# Familamp.net
KiCad netlist of a schematic drawn in EAGLE
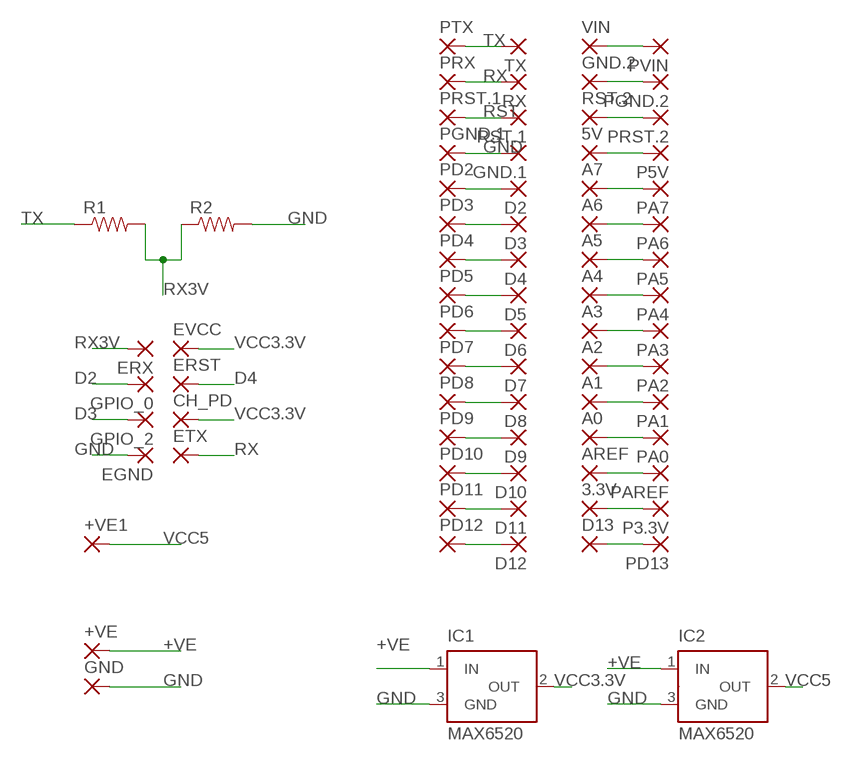
[diagram p0: schematic, sheet 1]

(export (version "E")
  (design (tool "Eeschema 10.0.6"))
  (components
    (comp (ref "+VE")
      (value "2,15/1,0")
      (footprint "eagle-import:2,15_1,0")
      (libsource (lib "eagle-import") (part "2,15/1,0"))
    )
    (comp (ref "+VE1")
      (value "2,15/1,0")
      (footprint "eagle-import:2,15_1,0")
      (libsource (lib "eagle-import") (part "2,15/1,0"))
    )
    (comp (ref "3.3V")
      (value "1,6/0,9")
      (footprint "eagle-import:1,6_0,9")
      (libsource (lib "eagle-import") (part "1,6/0,9"))
    )
    (comp (ref "5V")
      (value "1,6/0,9")
      (footprint "eagle-import:1,6_0,9")
      (libsource (lib "eagle-import") (part "1,6/0,9"))
    )
    (comp (ref "A0")
      (value "1,6/0,9")
      (footprint "eagle-import:1,6_0,9")
      (libsource (lib "eagle-import") (part "1,6/0,9"))
    )
    (comp (ref "A1")
      (value "1,6/0,9")
      (footprint "eagle-import:1,6_0,9")
      (libsource (lib "eagle-import") (part "1,6/0,9"))
    )
    (comp (ref "A2")
      (value "1,6/0,9")
      (footprint "eagle-import:1,6_0,9")
      (libsource (lib "eagle-import") (part "1,6/0,9"))
    )
    (comp (ref "A3")
      (value "1,6/0,9")
      (footprint "eagle-import:1,6_0,9")
      (libsource (lib "eagle-import") (part "1,6/0,9"))
    )
    (comp (ref "A4")
      (value "1,6/0,9")
      (footprint "eagle-import:1,6_0,9")
      (libsource (lib "eagle-import") (part "1,6/0,9"))
    )
    (comp (ref "A5")
      (value "1,6/0,9")
      (footprint "eagle-import:1,6_0,9")
      (libsource (lib "eagle-import") (part "1,6/0,9"))
    )
    (comp (ref "A6")
      (value "1,6/0,9")
      (footprint "eagle-import:1,6_0,9")
      (libsource (lib "eagle-import") (part "1,6/0,9"))
    )
    (comp (ref "A7")
      (value "1,6/0,9")
      (footprint "eagle-import:1,6_0,9")
      (libsource (lib "eagle-import") (part "1,6/0,9"))
    )
    (comp (ref "AREF")
      (value "1,6/0,9")
      (footprint "eagle-import:1,6_0,9")
      (libsource (lib "eagle-import") (part "1,6/0,9"))
    )
    (comp (ref "CH_PD")
      (value "2,15/1,0")
      (footprint "eagle-import:2,15_1,0")
      (libsource (lib "eagle-import") (part "2,15/1,0"))
    )
    (comp (ref "D2")
      (value "1,6/0,9")
      (footprint "eagle-import:1,6_0,9")
      (libsource (lib "eagle-import") (part "1,6/0,9"))
    )
    (comp (ref "D3")
      (value "1,6/0,9")
      (footprint "eagle-import:1,6_0,9")
      (libsource (lib "eagle-import") (part "1,6/0,9"))
    )
    (comp (ref "D4")
      (value "1,6/0,9")
      (footprint "eagle-import:1,6_0,9")
      (libsource (lib "eagle-import") (part "1,6/0,9"))
    )
    (comp (ref "D5")
      (value "1,6/0,9")
      (footprint "eagle-import:1,6_0,9")
      (libsource (lib "eagle-import") (part "1,6/0,9"))
    )
    (comp (ref "D6")
      (value "1,6/0,9")
      (footprint "eagle-import:1,6_0,9")
      (libsource (lib "eagle-import") (part "1,6/0,9"))
    )
    (comp (ref "D7")
      (value "1,6/0,9")
      (footprint "eagle-import:1,6_0,9")
      (libsource (lib "eagle-import") (part "1,6/0,9"))
    )
    (comp (ref "D8")
      (value "1,6/0,9")
      (footprint "eagle-import:1,6_0,9")
      (libsource (lib "eagle-import") (part "1,6/0,9"))
    )
    (comp (ref "D9")
      (value "1,6/0,9")
      (footprint "eagle-import:1,6_0,9")
      (libsource (lib "eagle-import") (part "1,6/0,9"))
    )
    (comp (ref "D10")
      (value "1,6/0,9")
      (footprint "eagle-import:1,6_0,9")
      (libsource (lib "eagle-import") (part "1,6/0,9"))
    )
    (comp (ref "D11")
      (value "1,6/0,9")
      (footprint "eagle-import:1,6_0,9")
      (libsource (lib "eagle-import") (part "1,6/0,9"))
    )
    (comp (ref "D12")
      (value "1,6/0,9")
      (footprint "eagle-import:1,6_0,9")
      (libsource (lib "eagle-import") (part "1,6/0,9"))
    )
    (comp (ref "D13")
      (value "1,6/0,9")
      (footprint "eagle-import:1,6_0,9")
      (libsource (lib "eagle-import") (part "1,6/0,9"))
    )
    (comp (ref "EGND")
      (value "2,15/1,0")
      (footprint "eagle-import:2,15_1,0")
      (libsource (lib "eagle-import") (part "2,15/1,0"))
    )
    (comp (ref "ERST")
      (value "2,15/1,0")
      (footprint "eagle-import:2,15_1,0")
      (libsource (lib "eagle-import") (part "2,15/1,0"))
    )
    (comp (ref "ERX")
      (value "2,15/1,0")
      (footprint "eagle-import:2,15_1,0")
      (libsource (lib "eagle-import") (part "2,15/1,0"))
    )
    (comp (ref "ETX")
      (value "2,15/1,0")
      (footprint "eagle-import:2,15_1,0")
      (libsource (lib "eagle-import") (part "2,15/1,0"))
    )
    (comp (ref "EVCC")
      (value "2,15/1,0")
      (footprint "eagle-import:2,15_1,0")
      (libsource (lib "eagle-import") (part "2,15/1,0"))
    )
    (comp (ref "GND")
      (value "2,15/1,0")
      (footprint "eagle-import:2,15_1,0")
      (libsource (lib "eagle-import") (part "2,15/1,0"))
    )
    (comp (ref "GND.1")
      (value "1,6/0,9")
      (footprint "eagle-import:1,6_0,9")
      (libsource (lib "eagle-import") (part "1,6/0,9"))
    )
    (comp (ref "GND.2")
      (value "1,6/0,9")
      (footprint "eagle-import:1,6_0,9")
      (libsource (lib "eagle-import") (part "1,6/0,9"))
    )
    (comp (ref "GPIO_0")
      (value "2,15/1,0")
      (footprint "eagle-import:2,15_1,0")
      (libsource (lib "eagle-import") (part "2,15/1,0"))
    )
    (comp (ref "GPIO_2")
      (value "2,15/1,0")
      (footprint "eagle-import:2,15_1,0")
      (libsource (lib "eagle-import") (part "2,15/1,0"))
    )
    (comp (ref "IC1")
      (value "MAX6520")
      (footprint "eagle-import:SOT23")
      (fields (field (name "MF") "MAXIM") (field (name "MPN") "MAX6520EUR-T"))
      (libsource (lib "eagle-import") (part "MAX6520"))
    )
    (comp (ref "IC2")
      (value "MAX6520")
      (footprint "eagle-import:SOT23")
      (fields (field (name "MF") "MAXIM") (field (name "MPN") "MAX6520EUR-T"))
      (libsource (lib "eagle-import") (part "MAX6520"))
    )
    (comp (ref "P3.3V")
      (value "1,6/0,9")
      (footprint "eagle-import:1,6_0,9")
      (libsource (lib "eagle-import") (part "1,6/0,9"))
    )
    (comp (ref "P5V")
      (value "1,6/0,9")
      (footprint "eagle-import:1,6_0,9")
      (libsource (lib "eagle-import") (part "1,6/0,9"))
    )
    (comp (ref "PA0")
      (value "1,6/0,9")
      (footprint "eagle-import:1,6_0,9")
      (libsource (lib "eagle-import") (part "1,6/0,9"))
    )
    (comp (ref "PA1")
      (value "1,6/0,9")
      (footprint "eagle-import:1,6_0,9")
      (libsource (lib "eagle-import") (part "1,6/0,9"))
    )
    (comp (ref "PA2")
      (value "1,6/0,9")
      (footprint "eagle-import:1,6_0,9")
      (libsource (lib "eagle-import") (part "1,6/0,9"))
    )
    (comp (ref "PA3")
      (value "1,6/0,9")
      (footprint "eagle-import:1,6_0,9")
      (libsource (lib "eagle-import") (part "1,6/0,9"))
    )
    (comp (ref "PA4")
      (value "1,6/0,9")
      (footprint "eagle-import:1,6_0,9")
      (libsource (lib "eagle-import") (part "1,6/0,9"))
    )
    (comp (ref "PA5")
      (value "1,6/0,9")
      (footprint "eagle-import:1,6_0,9")
      (libsource (lib "eagle-import") (part "1,6/0,9"))
    )
    (comp (ref "PA6")
      (value "1,6/0,9")
      (footprint "eagle-import:1,6_0,9")
      (libsource (lib "eagle-import") (part "1,6/0,9"))
    )
    (comp (ref "PA7")
      (value "1,6/0,9")
      (footprint "eagle-import:1,6_0,9")
      (libsource (lib "eagle-import") (part "1,6/0,9"))
    )
    (comp (ref "PAREF")
      (value "1,6/0,9")
      (footprint "eagle-import:1,6_0,9")
      (libsource (lib "eagle-import") (part "1,6/0,9"))
    )
    (comp (ref "PD2")
      (value "1,6/0,9")
      (footprint "eagle-import:1,6_0,9")
      (libsource (lib "eagle-import") (part "1,6/0,9"))
    )
    (comp (ref "PD3")
      (value "1,6/0,9")
      (footprint "eagle-import:1,6_0,9")
      (libsource (lib "eagle-import") (part "1,6/0,9"))
    )
    (comp (ref "PD4")
      (value "1,6/0,9")
      (footprint "eagle-import:1,6_0,9")
      (libsource (lib "eagle-import") (part "1,6/0,9"))
    )
    (comp (ref "PD5")
      (value "1,6/0,9")
      (footprint "eagle-import:1,6_0,9")
      (libsource (lib "eagle-import") (part "1,6/0,9"))
    )
    (comp (ref "PD6")
      (value "1,6/0,9")
      (footprint "eagle-import:1,6_0,9")
      (libsource (lib "eagle-import") (part "1,6/0,9"))
    )
    (comp (ref "PD7")
      (value "1,6/0,9")
      (footprint "eagle-import:1,6_0,9")
      (libsource (lib "eagle-import") (part "1,6/0,9"))
    )
    (comp (ref "PD8")
      (value "1,6/0,9")
      (footprint "eagle-import:1,6_0,9")
      (libsource (lib "eagle-import") (part "1,6/0,9"))
    )
    (comp (ref "PD9")
      (value "1,6/0,9")
      (footprint "eagle-import:1,6_0,9")
      (libsource (lib "eagle-import") (part "1,6/0,9"))
    )
    (comp (ref "PD10")
      (value "1,6/0,9")
      (footprint "eagle-import:1,6_0,9")
      (libsource (lib "eagle-import") (part "1,6/0,9"))
    )
    (comp (ref "PD11")
      (value "1,6/0,9")
      (footprint "eagle-import:1,6_0,9")
      (libsource (lib "eagle-import") (part "1,6/0,9"))
    )
    (comp (ref "PD12")
      (value "1,6/0,9")
      (footprint "eagle-import:1,6_0,9")
      (libsource (lib "eagle-import") (part "1,6/0,9"))
    )
    (comp (ref "PD13")
      (value "1,6/0,9")
      (footprint "eagle-import:1,6_0,9")
      (libsource (lib "eagle-import") (part "1,6/0,9"))
    )
    (comp (ref "PGND.1")
      (value "1,6/0,9")
      (footprint "eagle-import:1,6_0,9")
      (libsource (lib "eagle-import") (part "1,6/0,9"))
    )
    (comp (ref "PGND.2")
      (value "1,6/0,9")
      (footprint "eagle-import:1,6_0,9")
      (libsource (lib "eagle-import") (part "1,6/0,9"))
    )
    (comp (ref "PRST.1")
      (value "1,6/0,9")
      (footprint "eagle-import:1,6_0,9")
      (libsource (lib "eagle-import") (part "1,6/0,9"))
    )
    (comp (ref "PRST.2")
      (value "1,6/0,9")
      (footprint "eagle-import:1,6_0,9")
      (libsource (lib "eagle-import") (part "1,6/0,9"))
    )
    (comp (ref "PRX")
      (value "1,6/0,9")
      (footprint "eagle-import:1,6_0,9")
      (libsource (lib "eagle-import") (part "1,6/0,9"))
    )
    (comp (ref "PTX")
      (value "1,6/0,9")
      (footprint "eagle-import:1,6_0,9")
      (libsource (lib "eagle-import") (part "1,6/0,9"))
    )
    (comp (ref "PVIN")
      (value "1,6/0,9")
      (footprint "eagle-import:1,6_0,9")
      (libsource (lib "eagle-import") (part "1,6/0,9"))
    )
    (comp (ref "R1")
      (value "RESISTORPTH-1/2W")
      (footprint "eagle-import:AXIAL-0.5")
      (libsource (lib "eagle-import") (part "RESISTORPTH-1/2W"))
    )
    (comp (ref "R2")
      (value "RESISTORPTH-1/2W")
      (footprint "eagle-import:AXIAL-0.5")
      (libsource (lib "eagle-import") (part "RESISTORPTH-1/2W"))
    )
    (comp (ref "RST.1")
      (value "1,6/0,9")
      (footprint "eagle-import:1,6_0,9")
      (libsource (lib "eagle-import") (part "1,6/0,9"))
    )
    (comp (ref "RST.2")
      (value "1,6/0,9")
      (footprint "eagle-import:1,6_0,9")
      (libsource (lib "eagle-import") (part "1,6/0,9"))
    )
    (comp (ref "RX")
      (value "1,6/0,9")
      (footprint "eagle-import:1,6_0,9")
      (libsource (lib "eagle-import") (part "1,6/0,9"))
    )
    (comp (ref "TX")
      (value "1,6/0,9")
      (footprint "eagle-import:1,6_0,9")
      (libsource (lib "eagle-import") (part "1,6/0,9"))
    )
    (comp (ref "VIN")
      (value "1,6/0,9")
      (footprint "eagle-import:1,6_0,9")
      (libsource (lib "eagle-import") (part "1,6/0,9"))
    )
  )
  (nets
    (net (code "1") (name "/+VE") (class "Default")
      (node (ref "+VE") (pin "1") (pinfunction "P_1") (pintype "passive"))
      (node (ref "IC1") (pin "1") (pinfunction "IN_1") (pintype "input"))
      (node (ref "IC2") (pin "1") (pinfunction "IN_1") (pintype "input"))
      (node (ref "PVIN") (pin "1") (pinfunction "P_1") (pintype "passive"))
      (node (ref "VIN") (pin "1") (pinfunction "P_1") (pintype "passive"))
    )
    (net (code "2") (name "/D2") (class "Default")
      (node (ref "D2") (pin "1") (pinfunction "P_1") (pintype "passive"))
      (node (ref "GPIO_0") (pin "1") (pinfunction "P_1") (pintype "passive"))
      (node (ref "PD2") (pin "1") (pinfunction "P_1") (pintype "passive"))
    )
    (net (code "3") (name "/D3") (class "Default")
      (node (ref "D3") (pin "1") (pinfunction "P_1") (pintype "passive"))
      (node (ref "GPIO_2") (pin "1") (pinfunction "P_1") (pintype "passive"))
      (node (ref "PD3") (pin "1") (pinfunction "P_1") (pintype "passive"))
    )
    (net (code "4") (name "/D4") (class "Default")
      (node (ref "D4") (pin "1") (pinfunction "P_1") (pintype "passive"))
      (node (ref "ERST") (pin "1") (pinfunction "P_1") (pintype "passive"))
      (node (ref "PD4") (pin "1") (pinfunction "P_1") (pintype "passive"))
    )
    (net (code "5") (name "/GND") (class "Default")
      (node (ref "EGND") (pin "1") (pinfunction "P_1") (pintype "passive"))
      (node (ref "GND") (pin "1") (pinfunction "P_1") (pintype "passive"))
      (node (ref "GND.1") (pin "1") (pinfunction "P_1") (pintype "passive"))
      (node (ref "GND.2") (pin "1") (pinfunction "P_1") (pintype "passive"))
      (node (ref "IC1") (pin "3") (pinfunction "GND_3") (pintype "power_in"))
      (node (ref "IC2") (pin "3") (pinfunction "GND_3") (pintype "power_in"))
      (node (ref "PGND.1") (pin "1") (pinfunction "P_1") (pintype "passive"))
      (node (ref "PGND.2") (pin "1") (pinfunction "P_1") (pintype "passive"))
      (node (ref "R2") (pin "P$2") (pinfunction "2_P$2") (pintype "passive"))
    )
    (net (code "6") (name "/RST") (class "Default")
      (node (ref "PRST.1") (pin "1") (pinfunction "P_1") (pintype "passive"))
      (node (ref "RST.1") (pin "1") (pinfunction "P_1") (pintype "passive"))
    )
    (net (code "7") (name "/RX") (class "Default")
      (node (ref "ETX") (pin "1") (pinfunction "P_1") (pintype "passive"))
      (node (ref "PRX") (pin "1") (pinfunction "P_1") (pintype "passive"))
      (node (ref "RX") (pin "1") (pinfunction "P_1") (pintype "passive"))
    )
    (net (code "8") (name "/RX3V") (class "Default")
      (node (ref "ERX") (pin "1") (pinfunction "P_1") (pintype "passive"))
      (node (ref "R1") (pin "P$2") (pinfunction "2_P$2") (pintype "passive"))
      (node (ref "R2") (pin "P$1") (pinfunction "1_P$1") (pintype "passive"))
    )
    (net (code "9") (name "/TX") (class "Default")
      (node (ref "PTX") (pin "1") (pinfunction "P_1") (pintype "passive"))
      (node (ref "R1") (pin "P$1") (pinfunction "1_P$1") (pintype "passive"))
      (node (ref "TX") (pin "1") (pinfunction "P_1") (pintype "passive"))
    )
    (net (code "10") (name "/VCC3.3V") (class "Default")
      (node (ref "CH_PD") (pin "1") (pinfunction "P_1") (pintype "passive"))
      (node (ref "EVCC") (pin "1") (pinfunction "P_1") (pintype "passive"))
      (node (ref "IC1") (pin "2") (pinfunction "OUT_2") (pintype "output"))
    )
    (net (code "11") (name "/VCC5") (class "Default")
      (node (ref "+VE1") (pin "1") (pinfunction "P_1") (pintype "passive"))
      (node (ref "IC2") (pin "2") (pinfunction "OUT_2") (pintype "output"))
    )
    (net (code "12") (name "Net-(3.3V-P)") (class "Default")
      (node (ref "3.3V") (pin "1") (pinfunction "P_1") (pintype "passive"))
      (node (ref "P3.3V") (pin "1") (pinfunction "P_1") (pintype "passive"))
    )
    (net (code "13") (name "Net-(5V-P)") (class "Default")
      (node (ref "5V") (pin "1") (pinfunction "P_1") (pintype "passive"))
      (node (ref "P5V") (pin "1") (pinfunction "P_1") (pintype "passive"))
    )
    (net (code "14") (name "Net-(A0-P)") (class "Default")
      (node (ref "A0") (pin "1") (pinfunction "P_1") (pintype "passive"))
      (node (ref "PA0") (pin "1") (pinfunction "P_1") (pintype "passive"))
    )
    (net (code "15") (name "Net-(A1-P)") (class "Default")
      (node (ref "A1") (pin "1") (pinfunction "P_1") (pintype "passive"))
      (node (ref "PA1") (pin "1") (pinfunction "P_1") (pintype "passive"))
    )
    (net (code "16") (name "Net-(A2-P)") (class "Default")
      (node (ref "A2") (pin "1") (pinfunction "P_1") (pintype "passive"))
      (node (ref "PA2") (pin "1") (pinfunction "P_1") (pintype "passive"))
    )
    (net (code "17") (name "Net-(A3-P)") (class "Default")
      (node (ref "A3") (pin "1") (pinfunction "P_1") (pintype "passive"))
      (node (ref "PA3") (pin "1") (pinfunction "P_1") (pintype "passive"))
    )
    (net (code "18") (name "Net-(A4-P)") (class "Default")
      (node (ref "A4") (pin "1") (pinfunction "P_1") (pintype "passive"))
      (node (ref "PA4") (pin "1") (pinfunction "P_1") (pintype "passive"))
    )
    (net (code "19") (name "Net-(A5-P)") (class "Default")
      (node (ref "A5") (pin "1") (pinfunction "P_1") (pintype "passive"))
      (node (ref "PA5") (pin "1") (pinfunction "P_1") (pintype "passive"))
    )
    (net (code "20") (name "Net-(A6-P)") (class "Default")
      (node (ref "A6") (pin "1") (pinfunction "P_1") (pintype "passive"))
      (node (ref "PA6") (pin "1") (pinfunction "P_1") (pintype "passive"))
    )
    (net (code "21") (name "Net-(A7-P)") (class "Default")
      (node (ref "A7") (pin "1") (pinfunction "P_1") (pintype "passive"))
      (node (ref "PA7") (pin "1") (pinfunction "P_1") (pintype "passive"))
    )
    (net (code "22") (name "Net-(AREF-P)") (class "Default")
      (node (ref "AREF") (pin "1") (pinfunction "P_1") (pintype "passive"))
      (node (ref "PAREF") (pin "1") (pinfunction "P_1") (pintype "passive"))
    )
    (net (code "23") (name "Net-(D5-P)") (class "Default")
      (node (ref "D5") (pin "1") (pinfunction "P_1") (pintype "passive"))
      (node (ref "PD5") (pin "1") (pinfunction "P_1") (pintype "passive"))
    )
    (net (code "24") (name "Net-(D6-P)") (class "Default")
      (node (ref "D6") (pin "1") (pinfunction "P_1") (pintype "passive"))
      (node (ref "PD6") (pin "1") (pinfunction "P_1") (pintype "passive"))
    )
    (net (code "25") (name "Net-(D7-P)") (class "Default")
      (node (ref "D7") (pin "1") (pinfunction "P_1") (pintype "passive"))
      (node (ref "PD7") (pin "1") (pinfunction "P_1") (pintype "passive"))
    )
    (net (code "26") (name "Net-(D8-P)") (class "Default")
      (node (ref "D8") (pin "1") (pinfunction "P_1") (pintype "passive"))
      (node (ref "PD8") (pin "1") (pinfunction "P_1") (pintype "passive"))
    )
    (net (code "27") (name "Net-(D9-P)") (class "Default")
      (node (ref "D9") (pin "1") (pinfunction "P_1") (pintype "passive"))
      (node (ref "PD9") (pin "1") (pinfunction "P_1") (pintype "passive"))
    )
    (net (code "28") (name "Net-(D10-P)") (class "Default")
      (node (ref "D10") (pin "1") (pinfunction "P_1") (pintype "passive"))
      (node (ref "PD10") (pin "1") (pinfunction "P_1") (pintype "passive"))
    )
    (net (code "29") (name "Net-(D11-P)") (class "Default")
      (node (ref "D11") (pin "1") (pinfunction "P_1") (pintype "passive"))
      (node (ref "PD11") (pin "1") (pinfunction "P_1") (pintype "passive"))
    )
    (net (code "30") (name "Net-(D12-P)") (class "Default")
      (node (ref "D12") (pin "1") (pinfunction "P_1") (pintype "passive"))
      (node (ref "PD12") (pin "1") (pinfunction "P_1") (pintype "passive"))
    )
    (net (code "31") (name "Net-(D13-P)") (class "Default")
      (node (ref "D13") (pin "1") (pinfunction "P_1") (pintype "passive"))
      (node (ref "PD13") (pin "1") (pinfunction "P_1") (pintype "passive"))
    )
    (net (code "32") (name "Net-(PRST.2-P)") (class "Default")
      (node (ref "PRST.2") (pin "1") (pinfunction "P_1") (pintype "passive"))
      (node (ref "RST.2") (pin "1") (pinfunction "P_1") (pintype "passive"))
    )
  )
)
